# main.net
KiCad netlist of a schematic drawn in EAGLE
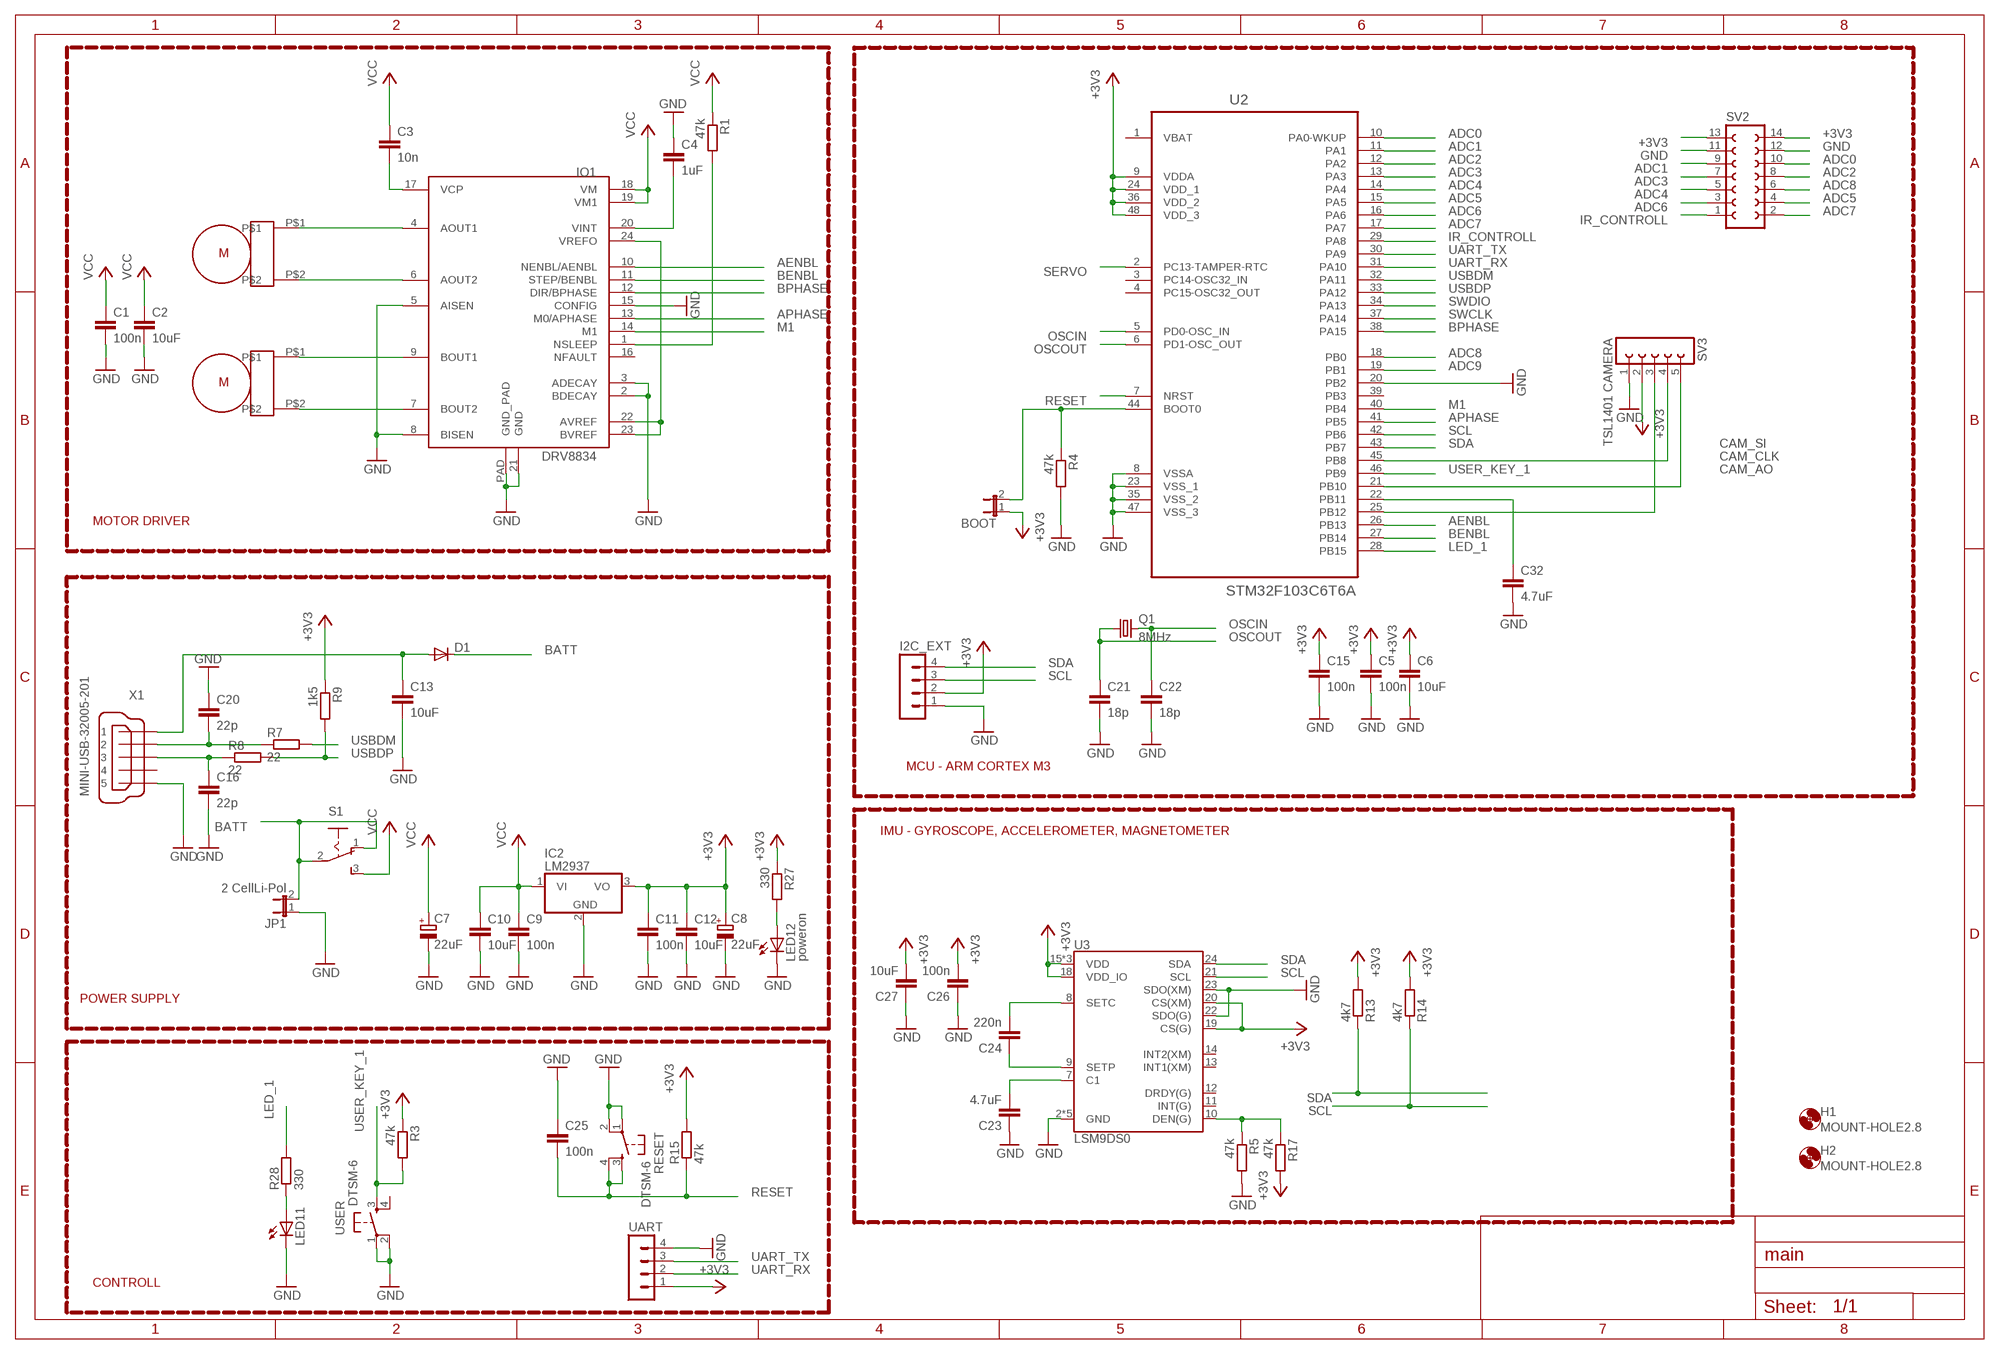
[diagram p0: schematic, sheet 1]

(export (version "E")
  (design (tool "Eeschema 10.0.6"))
  (components
    (comp (ref "BOOT")
      (value "JP1E")
      (footprint "eagle-import:JP1")
      (libsource (lib "eagle-import") (part "JP1E"))
    )
    (comp (ref "C1")
      (value "100n")
      (footprint "eagle-import:C1206")
      (libsource (lib "eagle-import") (part "C-EUC1206"))
    )
    (comp (ref "C2")
      (value "10uF")
      (footprint "eagle-import:C1206")
      (libsource (lib "eagle-import") (part "C-EUC1206"))
    )
    (comp (ref "C3")
      (value "10n")
      (footprint "eagle-import:C1206")
      (libsource (lib "eagle-import") (part "C-EUC1206"))
    )
    (comp (ref "C4")
      (value "1uF")
      (footprint "eagle-import:C1206")
      (libsource (lib "eagle-import") (part "C-EUC1206"))
    )
    (comp (ref "C5")
      (value "100n")
      (footprint "eagle-import:C0805")
      (libsource (lib "eagle-import") (part "C-EUC0805"))
    )
    (comp (ref "C6")
      (value "10uF")
      (footprint "eagle-import:C0805")
      (libsource (lib "eagle-import") (part "C-EUC0805"))
    )
    (comp (ref "C7")
      (value "22uF")
      (footprint "eagle-import:153CLV-0505")
      (libsource (lib "eagle-import") (part "CPOL-EU153CLV-0505"))
    )
    (comp (ref "C8")
      (value "22uF")
      (footprint "eagle-import:153CLV-0505")
      (libsource (lib "eagle-import") (part "CPOL-EU153CLV-0505"))
    )
    (comp (ref "C9")
      (value "100n")
      (footprint "eagle-import:C0805")
      (libsource (lib "eagle-import") (part "C-EUC0805"))
    )
    (comp (ref "C10")
      (value "10uF")
      (footprint "eagle-import:C0805")
      (libsource (lib "eagle-import") (part "C-EUC0805"))
    )
    (comp (ref "C11")
      (value "100n")
      (footprint "eagle-import:C0805")
      (libsource (lib "eagle-import") (part "C-EUC0805"))
    )
    (comp (ref "C12")
      (value "10uF")
      (footprint "eagle-import:C0805")
      (libsource (lib "eagle-import") (part "C-EUC0805"))
    )
    (comp (ref "C13")
      (value "10uF")
      (footprint "eagle-import:C0805")
      (libsource (lib "eagle-import") (part "C-EUC0805"))
    )
    (comp (ref "C15")
      (value "100n")
      (footprint "eagle-import:C0805")
      (libsource (lib "eagle-import") (part "C-EUC0805"))
    )
    (comp (ref "C16")
      (value "22p")
      (footprint "eagle-import:C0805")
      (libsource (lib "eagle-import") (part "C-EUC0805"))
    )
    (comp (ref "C20")
      (value "22p")
      (footprint "eagle-import:C0805")
      (libsource (lib "eagle-import") (part "C-EUC0805"))
    )
    (comp (ref "C21")
      (value "18p")
      (footprint "eagle-import:C0805")
      (libsource (lib "eagle-import") (part "C-EUC0805"))
    )
    (comp (ref "C22")
      (value "18p")
      (footprint "eagle-import:C0805")
      (libsource (lib "eagle-import") (part "C-EUC0805"))
    )
    (comp (ref "C23")
      (value "4.7uF")
      (footprint "eagle-import:C0805")
      (libsource (lib "eagle-import") (part "C-EUC0805"))
    )
    (comp (ref "C24")
      (value "220n")
      (footprint "eagle-import:C0805")
      (libsource (lib "eagle-import") (part "C-EUC0805"))
    )
    (comp (ref "C25")
      (value "100n")
      (footprint "eagle-import:C0805")
      (libsource (lib "eagle-import") (part "C-EUC0805"))
    )
    (comp (ref "C26")
      (value "100n")
      (footprint "eagle-import:C0805")
      (libsource (lib "eagle-import") (part "C-EUC0805"))
    )
    (comp (ref "C27")
      (value "10uF")
      (footprint "eagle-import:C0805")
      (libsource (lib "eagle-import") (part "C-EUC0805"))
    )
    (comp (ref "C32")
      (value "4.7uF")
      (footprint "eagle-import:C0805")
      (libsource (lib "eagle-import") (part "C-EUC0805"))
    )
    (comp (ref "D1")
      (value "DIODE-SMB")
      (footprint "eagle-import:SMB")
      (libsource (lib "eagle-import") (part "DIODE-SMB"))
    )
    (comp (ref "H1")
      (value "MOUNT-HOLE2.8")
      (footprint "eagle-import:2,8")
      (libsource (lib "eagle-import") (part "MOUNT-HOLE2.8"))
    )
    (comp (ref "H2")
      (value "MOUNT-HOLE2.8")
      (footprint "eagle-import:2,8")
      (libsource (lib "eagle-import") (part "MOUNT-HOLE2.8"))
    )
    (comp (ref "I2C_EXT")
      (value "MA04-1")
      (footprint "eagle-import:MA04-1")
      (libsource (lib "eagle-import") (part "MA04-1"))
    )
    (comp (ref "IC2")
      (value "LM2937")
      (footprint "eagle-import:TO263-3")
      (libsource (lib "eagle-import") (part "LM2937"))
    )
    (comp (ref "IO1")
      (value "DRV8834")
      (footprint "eagle-import:DRV8834_PCK")
      (libsource (lib "eagle-import") (part "DRV8834"))
    )
    (comp (ref "JP1")
      (value "2 CellLi-Pol")
      (footprint "eagle-import:JP1")
      (libsource (lib "eagle-import") (part "JP1E"))
    )
    (comp (ref "LED11")
      (value "LEDCHIPLED_1206")
      (footprint "eagle-import:CHIPLED_1206")
      (libsource (lib "eagle-import") (part "LEDCHIPLED_1206"))
    )
    (comp (ref "LED12")
      (value "poweron")
      (footprint "eagle-import:CHIPLED_1206")
      (libsource (lib "eagle-import") (part "LEDCHIPLED_1206"))
    )
    (comp (ref "Q1")
      (value "8MHz")
      (footprint "eagle-import:CTS406")
      (libsource (lib "eagle-import") (part "CRYSTALCTS406"))
    )
    (comp (ref "R1")
      (value "47k")
      (footprint "eagle-import:M1206")
      (libsource (lib "eagle-import") (part "R-EU_M1206"))
    )
    (comp (ref "R3")
      (value "47k")
      (footprint "eagle-import:M0805")
      (libsource (lib "eagle-import") (part "R-EU_M0805"))
    )
    (comp (ref "R4")
      (value "47k")
      (footprint "eagle-import:M0805")
      (libsource (lib "eagle-import") (part "R-EU_M0805"))
    )
    (comp (ref "R5")
      (value "47k")
      (footprint "eagle-import:M0805")
      (libsource (lib "eagle-import") (part "R-EU_M0805"))
    )
    (comp (ref "R7")
      (value "22")
      (footprint "eagle-import:M0805")
      (libsource (lib "eagle-import") (part "R-EU_M0805"))
    )
    (comp (ref "R8")
      (value "22")
      (footprint "eagle-import:M0805")
      (libsource (lib "eagle-import") (part "R-EU_M0805"))
    )
    (comp (ref "R9")
      (value "1k5")
      (footprint "eagle-import:M0805")
      (libsource (lib "eagle-import") (part "R-EU_M0805"))
    )
    (comp (ref "R13")
      (value "4k7")
      (footprint "eagle-import:M0805")
      (libsource (lib "eagle-import") (part "R-EU_M0805"))
    )
    (comp (ref "R14")
      (value "4k7")
      (footprint "eagle-import:M0805")
      (libsource (lib "eagle-import") (part "R-EU_M0805"))
    )
    (comp (ref "R15")
      (value "47k")
      (footprint "eagle-import:M0805")
      (libsource (lib "eagle-import") (part "R-EU_M0805"))
    )
    (comp (ref "R17")
      (value "47k")
      (footprint "eagle-import:M0805")
      (libsource (lib "eagle-import") (part "R-EU_M0805"))
    )
    (comp (ref "R27")
      (value "330")
      (footprint "eagle-import:M0805")
      (libsource (lib "eagle-import") (part "R-EU_M0805"))
    )
    (comp (ref "R28")
      (value "330")
      (footprint "eagle-import:M0805")
      (libsource (lib "eagle-import") (part "R-EU_M0805"))
    )
    (comp (ref "RESET")
      (value "DTSM-6")
      (footprint "eagle-import:DTSM-6")
      (libsource (lib "eagle-import") (part "DTSM-6"))
    )
    (comp (ref "S1")
      (value "255SB")
      (footprint "eagle-import:255SB")
      (libsource (lib "eagle-import") (part "255SB"))
    )
    (comp (ref "SV2")
      (value "FE07-2")
      (footprint "eagle-import:FE07-2")
      (libsource (lib "eagle-import") (part "FE07-2"))
    )
    (comp (ref "SV3")
      (value "TSL1401 CAMERA")
      (footprint "eagle-import:FE05-1")
      (libsource (lib "eagle-import") (part "FE05-1"))
    )
    (comp (ref "U$1")
      (value "MICRO_METAL_GEAR_MOTOR")
      (footprint "eagle-import:MICRO_METAL_GEAR_MOTOR")
      (libsource (lib "eagle-import") (part "MICRO_METAL_GEAR_MOTOR"))
    )
    (comp (ref "U$2")
      (value "MICRO_METAL_GEAR_MOTOR")
      (footprint "eagle-import:MICRO_METAL_GEAR_MOTOR")
      (libsource (lib "eagle-import") (part "MICRO_METAL_GEAR_MOTOR"))
    )
    (comp (ref "U2")
      (value "STM32F103C6T6A")
      (footprint "eagle-import:QFP50P900X900X160-48N")
      (libsource (lib "eagle-import") (part "STM32F103C6T6A"))
    )
    (comp (ref "U3")
      (value "LSM9DS0")
      (footprint "eagle-import:LGA-24")
      (libsource (lib "eagle-import") (part "LSM9DS0"))
    )
    (comp (ref "UART")
      (value "MA04-1")
      (footprint "eagle-import:MA04-1")
      (libsource (lib "eagle-import") (part "MA04-1"))
    )
    (comp (ref "USER")
      (value "DTSM-6")
      (footprint "eagle-import:DTSM-6")
      (libsource (lib "eagle-import") (part "DTSM-6"))
    )
    (comp (ref "X1")
      (value "MINI-USB-32005-201")
      (footprint "eagle-import:32005-201")
      (libsource (lib "eagle-import") (part "MINI-USB-32005-201"))
    )
  )
  (nets
    (net (code "1") (name "+3V3") (class "Default")
      (node (ref "BOOT") (pin "1") (pinfunction "1_1") (pintype "passive"))
      (node (ref "C11") (pin "1") (pinfunction "1_1") (pintype "passive"))
      (node (ref "C12") (pin "1") (pinfunction "1_1") (pintype "passive"))
      (node (ref "C15") (pin "1") (pinfunction "1_1") (pintype "passive"))
      (node (ref "C26") (pin "2") (pinfunction "2_2") (pintype "passive"))
      (node (ref "C27") (pin "2") (pinfunction "2_2") (pintype "passive"))
      (node (ref "C5") (pin "1") (pinfunction "1_1") (pintype "passive"))
      (node (ref "C6") (pin "1") (pinfunction "1_1") (pintype "passive"))
      (node (ref "C8") (pin "+") (pinfunction "+_+") (pintype "passive"))
      (node (ref "I2C_EXT") (pin "2") (pinfunction "2_2") (pintype "passive"))
      (node (ref "IC2") (pin "3") (pinfunction "VO_3") (pintype "passive"))
      (node (ref "R13") (pin "2") (pinfunction "2_2") (pintype "passive"))
      (node (ref "R14") (pin "2") (pinfunction "2_2") (pintype "passive"))
      (node (ref "R15") (pin "2") (pinfunction "2_2") (pintype "passive"))
      (node (ref "R17") (pin "2") (pinfunction "2_2") (pintype "passive"))
      (node (ref "R27") (pin "1") (pinfunction "1_1") (pintype "passive"))
      (node (ref "R3") (pin "1") (pinfunction "1_1") (pintype "passive"))
      (node (ref "R9") (pin "1") (pinfunction "1_1") (pintype "passive"))
      (node (ref "SV2") (pin "13") (pinfunction "13_13") (pintype "passive"))
      (node (ref "SV2") (pin "14") (pinfunction "14_14") (pintype "passive"))
      (node (ref "SV3") (pin "2") (pinfunction "2_2") (pintype "passive"))
      (node (ref "U2") (pin "24") (pinfunction "VDD_1_24") (pintype "power_in"))
      (node (ref "U2") (pin "36") (pinfunction "VDD_2_36") (pintype "power_in"))
      (node (ref "U2") (pin "48") (pinfunction "VDD_3_48") (pintype "power_in"))
      (node (ref "U2") (pin "9") (pinfunction "VDDA_9") (pintype "power_in"))
      (node (ref "U3") (pin "15") (pinfunction "VDD_15") (pintype "bidirectional"))
      (node (ref "U3") (pin "16") (pinfunction "VDD_16") (pintype "bidirectional"))
      (node (ref "U3") (pin "17") (pinfunction "VDD_17") (pintype "bidirectional"))
      (node (ref "U3") (pin "18") (pinfunction "VDD_IO_18") (pintype "bidirectional"))
      (node (ref "U3") (pin "19") (pinfunction "CS(G)_19") (pintype "bidirectional"))
      (node (ref "U3") (pin "20") (pinfunction "CS(XM)_20") (pintype "bidirectional"))
      (node (ref "UART") (pin "1") (pinfunction "1_1") (pintype "passive"))
    )
    (net (code "2") (name "/ADC0") (class "Default")
      (node (ref "SV2") (pin "10") (pinfunction "10_10") (pintype "passive"))
      (node (ref "U2") (pin "10") (pinfunction "PA0-WKUP_10") (pintype "bidirectional"))
    )
    (net (code "3") (name "/ADC1") (class "Default")
      (node (ref "SV2") (pin "9") (pinfunction "9_9") (pintype "passive"))
      (node (ref "U2") (pin "11") (pinfunction "PA1_11") (pintype "bidirectional"))
    )
    (net (code "4") (name "/ADC2") (class "Default")
      (node (ref "SV2") (pin "8") (pinfunction "8_8") (pintype "passive"))
      (node (ref "U2") (pin "12") (pinfunction "PA2_12") (pintype "bidirectional"))
    )
    (net (code "5") (name "/ADC3") (class "Default")
      (node (ref "SV2") (pin "7") (pinfunction "7_7") (pintype "passive"))
      (node (ref "U2") (pin "13") (pinfunction "PA3_13") (pintype "bidirectional"))
    )
    (net (code "6") (name "/ADC4") (class "Default")
      (node (ref "SV2") (pin "5") (pinfunction "5_5") (pintype "passive"))
      (node (ref "U2") (pin "14") (pinfunction "PA4_14") (pintype "bidirectional"))
    )
    (net (code "7") (name "/ADC5") (class "Default")
      (node (ref "SV2") (pin "4") (pinfunction "4_4") (pintype "passive"))
      (node (ref "U2") (pin "15") (pinfunction "PA5_15") (pintype "bidirectional"))
    )
    (net (code "8") (name "/ADC6") (class "Default")
      (node (ref "SV2") (pin "3") (pinfunction "3_3") (pintype "passive"))
      (node (ref "U2") (pin "16") (pinfunction "PA6_16") (pintype "bidirectional"))
    )
    (net (code "9") (name "/ADC7") (class "Default")
      (node (ref "SV2") (pin "2") (pinfunction "2_2") (pintype "passive"))
      (node (ref "U2") (pin "17") (pinfunction "PA7_17") (pintype "bidirectional"))
    )
    (net (code "10") (name "/ADC8") (class "Default")
      (node (ref "SV2") (pin "6") (pinfunction "6_6") (pintype "passive"))
      (node (ref "U2") (pin "18") (pinfunction "PB0_18") (pintype "bidirectional"))
    )
    (net (code "11") (name "/ADC9") (class "Default")
      (node (ref "U2") (pin "19") (pinfunction "PB1_19") (pintype "bidirectional"))
    )
    (net (code "12") (name "/AENBL") (class "Default")
      (node (ref "IO1") (pin "10") (pinfunction "NENBL/AENBL_10") (pintype "bidirectional"))
      (node (ref "U2") (pin "26") (pinfunction "PB13_26") (pintype "bidirectional"))
    )
    (net (code "13") (name "/APHASE") (class "Default")
      (node (ref "IO1") (pin "13") (pinfunction "M0/APHASE_13") (pintype "bidirectional"))
      (node (ref "U2") (pin "41") (pinfunction "PB5_41") (pintype "bidirectional"))
    )
    (net (code "14") (name "/BATT") (class "Default")
      (node (ref "D1") (pin "C") (pinfunction "C_C") (pintype "passive"))
      (node (ref "JP1") (pin "2") (pinfunction "2_2") (pintype "passive"))
      (node (ref "S1") (pin "1") (pinfunction "O_1") (pintype "passive"))
      (node (ref "S1") (pin "2") (pinfunction "P_2") (pintype "passive"))
    )
    (net (code "15") (name "/BENBL") (class "Default")
      (node (ref "IO1") (pin "11") (pinfunction "STEP/BENBL_11") (pintype "bidirectional"))
      (node (ref "U2") (pin "27") (pinfunction "PB14_27") (pintype "bidirectional"))
    )
    (net (code "16") (name "/BPHASE") (class "Default")
      (node (ref "IO1") (pin "12") (pinfunction "DIR/BPHASE_12") (pintype "bidirectional"))
      (node (ref "U2") (pin "38") (pinfunction "PA15_38") (pintype "bidirectional"))
    )
    (net (code "17") (name "/CAM_AO") (class "Default")
      (node (ref "SV3") (pin "3") (pinfunction "3_3") (pintype "passive"))
      (node (ref "U2") (pin "25") (pinfunction "PB12_25") (pintype "bidirectional"))
    )
    (net (code "18") (name "/CAM_CLK") (class "Default")
      (node (ref "SV3") (pin "4") (pinfunction "4_4") (pintype "passive"))
      (node (ref "U2") (pin "45") (pinfunction "PB8_45") (pintype "bidirectional"))
    )
    (net (code "19") (name "/CAM_SI") (class "Default")
      (node (ref "SV3") (pin "5") (pinfunction "5_5") (pintype "passive"))
      (node (ref "U2") (pin "21") (pinfunction "PB10_21") (pintype "bidirectional"))
    )
    (net (code "20") (name "/IR_CONTROLL") (class "Default")
      (node (ref "SV2") (pin "1") (pinfunction "1_1") (pintype "passive"))
      (node (ref "U2") (pin "29") (pinfunction "PA8_29") (pintype "bidirectional"))
    )
    (net (code "21") (name "/LED_1") (class "Default")
      (node (ref "R28") (pin "2") (pinfunction "2_2") (pintype "passive"))
      (node (ref "U2") (pin "28") (pinfunction "PB15_28") (pintype "bidirectional"))
    )
    (net (code "22") (name "/M1") (class "Default")
      (node (ref "IO1") (pin "14") (pinfunction "M1_14") (pintype "bidirectional"))
      (node (ref "U2") (pin "40") (pinfunction "PB4_40") (pintype "bidirectional"))
    )
    (net (code "23") (name "/OSCIN") (class "Default")
      (node (ref "C22") (pin "1") (pinfunction "1_1") (pintype "passive"))
      (node (ref "Q1") (pin "3") (pinfunction "2_3") (pintype "passive"))
      (node (ref "U2") (pin "5") (pinfunction "PD0-OSC_IN_5") (pintype "bidirectional"))
    )
    (net (code "24") (name "/OSCOUT") (class "Default")
      (node (ref "C21") (pin "1") (pinfunction "1_1") (pintype "passive"))
      (node (ref "Q1") (pin "1") (pinfunction "1_1") (pintype "passive"))
      (node (ref "U2") (pin "6") (pinfunction "PD1-OSC_OUT_6") (pintype "bidirectional"))
    )
    (net (code "25") (name "/RESET") (class "Default")
      (node (ref "C25") (pin "2") (pinfunction "2_2") (pintype "passive"))
      (node (ref "R15") (pin "1") (pinfunction "1_1") (pintype "passive"))
      (node (ref "RESET") (pin "3") (pinfunction "3_3") (pintype "passive"))
      (node (ref "RESET") (pin "4") (pinfunction "4_4") (pintype "passive"))
      (node (ref "U2") (pin "7") (pinfunction "NRST_7") (pintype "bidirectional"))
    )
    (net (code "26") (name "/SCL") (class "Default")
      (node (ref "I2C_EXT") (pin "3") (pinfunction "3_3") (pintype "passive"))
      (node (ref "R14") (pin "1") (pinfunction "1_1") (pintype "passive"))
      (node (ref "U2") (pin "42") (pinfunction "PB6_42") (pintype "bidirectional"))
      (node (ref "U3") (pin "21") (pinfunction "SCL_21") (pintype "bidirectional"))
    )
    (net (code "27") (name "/SDA") (class "Default")
      (node (ref "I2C_EXT") (pin "4") (pinfunction "4_4") (pintype "passive"))
      (node (ref "R13") (pin "1") (pinfunction "1_1") (pintype "passive"))
      (node (ref "U2") (pin "43") (pinfunction "PB7_43") (pintype "bidirectional"))
      (node (ref "U3") (pin "24") (pinfunction "SDA_24") (pintype "bidirectional"))
    )
    (net (code "28") (name "/SERVO") (class "Default")
      (node (ref "U2") (pin "2") (pinfunction "PC13-TAMPER-RTC_2") (pintype "bidirectional"))
    )
    (net (code "29") (name "/SWCLK") (class "Default")
      (node (ref "U2") (pin "37") (pinfunction "PA14_37") (pintype "bidirectional"))
    )
    (net (code "30") (name "/SWDIO") (class "Default")
      (node (ref "U2") (pin "34") (pinfunction "PA13_34") (pintype "bidirectional"))
    )
    (net (code "31") (name "/UART_RX") (class "Default")
      (node (ref "U2") (pin "31") (pinfunction "PA10_31") (pintype "bidirectional"))
      (node (ref "UART") (pin "2") (pinfunction "2_2") (pintype "passive"))
    )
    (net (code "32") (name "/UART_TX") (class "Default")
      (node (ref "U2") (pin "30") (pinfunction "PA9_30") (pintype "bidirectional"))
      (node (ref "UART") (pin "3") (pinfunction "3_3") (pintype "passive"))
    )
    (net (code "33") (name "/USBDM") (class "Default")
      (node (ref "R7") (pin "2") (pinfunction "2_2") (pintype "passive"))
      (node (ref "U2") (pin "32") (pinfunction "PA11_32") (pintype "bidirectional"))
    )
    (net (code "34") (name "/USBDP") (class "Default")
      (node (ref "R8") (pin "2") (pinfunction "2_2") (pintype "passive"))
      (node (ref "R9") (pin "2") (pinfunction "2_2") (pintype "passive"))
      (node (ref "U2") (pin "33") (pinfunction "PA12_33") (pintype "bidirectional"))
    )
    (net (code "35") (name "/USER_KEY_1") (class "Default")
      (node (ref "R3") (pin "2") (pinfunction "2_2") (pintype "passive"))
      (node (ref "U2") (pin "46") (pinfunction "PB9_46") (pintype "bidirectional"))
      (node (ref "USER") (pin "3") (pinfunction "3_3") (pintype "passive"))
    )
    (net (code "36") (name "/VBAT") (class "Default")
      (node (ref "U2") (pin "1") (pinfunction "VBAT_1") (pintype "power_in"))
    )
    (net (code "37") (name "GND") (class "Default")
      (node (ref "C1") (pin "2") (pinfunction "2_2") (pintype "passive"))
      (node (ref "C10") (pin "2") (pinfunction "2_2") (pintype "passive"))
      (node (ref "C11") (pin "2") (pinfunction "2_2") (pintype "passive"))
      (node (ref "C12") (pin "2") (pinfunction "2_2") (pintype "passive"))
      (node (ref "C13") (pin "2") (pinfunction "2_2") (pintype "passive"))
      (node (ref "C15") (pin "2") (pinfunction "2_2") (pintype "passive"))
      (node (ref "C16") (pin "2") (pinfunction "2_2") (pintype "passive"))
      (node (ref "C2") (pin "2") (pinfunction "2_2") (pintype "passive"))
      (node (ref "C20") (pin "1") (pinfunction "1_1") (pintype "passive"))
      (node (ref "C21") (pin "2") (pinfunction "2_2") (pintype "passive"))
      (node (ref "C22") (pin "2") (pinfunction "2_2") (pintype "passive"))
      (node (ref "C23") (pin "1") (pinfunction "1_1") (pintype "passive"))
      (node (ref "C25") (pin "1") (pinfunction "1_1") (pintype "passive"))
      (node (ref "C26") (pin "1") (pinfunction "1_1") (pintype "passive"))
      (node (ref "C27") (pin "1") (pinfunction "1_1") (pintype "passive"))
      (node (ref "C32") (pin "2") (pinfunction "2_2") (pintype "passive"))
      (node (ref "C4") (pin "1") (pinfunction "1_1") (pintype "passive"))
      (node (ref "C5") (pin "2") (pinfunction "2_2") (pintype "passive"))
      (node (ref "C6") (pin "2") (pinfunction "2_2") (pintype "passive"))
      (node (ref "C7") (pin "-") (pinfunction "-_-") (pintype "passive"))
      (node (ref "C8") (pin "-") (pinfunction "-_-") (pintype "passive"))
      (node (ref "C9") (pin "2") (pinfunction "2_2") (pintype "passive"))
      (node (ref "I2C_EXT") (pin "1") (pinfunction "1_1") (pintype "passive"))
      (node (ref "IC2") (pin "2") (pinfunction "GND_2") (pintype "passive"))
      (node (ref "IO1") (pin "15") (pinfunction "CONFIG_15") (pintype "bidirectional"))
      (node (ref "IO1") (pin "2") (pinfunction "BDECAY_2") (pintype "bidirectional"))
      (node (ref "IO1") (pin "21") (pinfunction "GND_21") (pintype "bidirectional"))
      (node (ref "IO1") (pin "3") (pinfunction "ADECAY_3") (pintype "bidirectional"))
      (node (ref "IO1") (pin "5") (pinfunction "AISEN_5") (pintype "bidirectional"))
      (node (ref "IO1") (pin "8") (pinfunction "BISEN_8") (pintype "bidirectional"))
      (node (ref "IO1") (pin "PAD") (pinfunction "GND_PAD_PAD") (pintype "bidirectional"))
      (node (ref "JP1") (pin "1") (pinfunction "1_1") (pintype "passive"))
      (node (ref "LED11") (pin "C") (pinfunction "C_C") (pintype "passive"))
      (node (ref "LED12") (pin "C") (pinfunction "C_C") (pintype "passive"))
      (node (ref "R4") (pin "2") (pinfunction "2_2") (pintype "passive"))
      (node (ref "R5") (pin "2") (pinfunction "2_2") (pintype "passive"))
      (node (ref "RESET") (pin "1") (pinfunction "1_1") (pintype "passive"))
      (node (ref "RESET") (pin "2") (pinfunction "2_2") (pintype "passive"))
      (node (ref "SV2") (pin "11") (pinfunction "11_11") (pintype "passive"))
      (node (ref "SV2") (pin "12") (pinfunction "12_12") (pintype "passive"))
      (node (ref "SV3") (pin "1") (pinfunction "1_1") (pintype "passive"))
      (node (ref "U2") (pin "20") (pinfunction "PB2_20") (pintype "bidirectional"))
      (node (ref "U2") (pin "23") (pinfunction "VSS_1_23") (pintype "passive"))
      (node (ref "U2") (pin "35") (pinfunction "VSS_2_35") (pintype "passive"))
      (node (ref "U2") (pin "47") (pinfunction "VSS_3_47") (pintype "passive"))
      (node (ref "U2") (pin "8") (pinfunction "VSSA_8") (pintype "passive"))
      (node (ref "U3") (pin "2") (pinfunction "GND_2") (pintype "bidirectional"))
      (node (ref "U3") (pin "22") (pinfunction "SDO(G)_22") (pintype "bidirectional"))
      (node (ref "U3") (pin "23") (pinfunction "SDO(XM)_23") (pintype "bidirectional"))
      (node (ref "U3") (pin "3") (pinfunction "GND_3") (pintype "bidirectional"))
      (node (ref "U3") (pin "4") (pinfunction "GND_4") (pintype "bidirectional"))
      (node (ref "U3") (pin "5") (pinfunction "GND_5") (pintype "bidirectional"))
      (node (ref "U3") (pin "6") (pinfunction "GND_6") (pintype "bidirectional"))
      (node (ref "UART") (pin "4") (pinfunction "4_4") (pintype "passive"))
      (node (ref "USER") (pin "1") (pinfunction "1_1") (pintype "passive"))
      (node (ref "USER") (pin "2") (pinfunction "2_2") (pintype "passive"))
      (node (ref "X1") (pin "5") (pinfunction "5_5") (pintype "passive"))
    )
    (net (code "38") (name "Net-(C13-Pad1)") (class "Default")
      (node (ref "C13") (pin "1") (pinfunction "1_1") (pintype "passive"))
      (node (ref "D1") (pin "A") (pinfunction "A_A") (pintype "passive"))
      (node (ref "X1") (pin "1") (pinfunction "1_1") (pintype "passive"))
    )
    (net (code "39") (name "Net-(C16-Pad1)") (class "Default")
      (node (ref "C16") (pin "1") (pinfunction "1_1") (pintype "passive"))
      (node (ref "R8") (pin "1") (pinfunction "1_1") (pintype "passive"))
      (node (ref "X1") (pin "3") (pinfunction "3_3") (pintype "passive"))
    )
    (net (code "40") (name "Net-(C20-Pad2)") (class "Default")
      (node (ref "C20") (pin "2") (pinfunction "2_2") (pintype "passive"))
      (node (ref "R7") (pin "1") (pinfunction "1_1") (pintype "passive"))
      (node (ref "X1") (pin "2") (pinfunction "2_2") (pintype "passive"))
    )
    (net (code "41") (name "Net-(IO1-AOUT1)") (class "Default")
      (node (ref "IO1") (pin "4") (pinfunction "AOUT1_4") (pintype "bidirectional"))
      (node (ref "U$1") (pin "P$1") (pinfunction "P$1_P$1") (pintype "bidirectional"))
    )
    (net (code "42") (name "Net-(IO1-AOUT2)") (class "Default")
      (node (ref "IO1") (pin "6") (pinfunction "AOUT2_6") (pintype "bidirectional"))
      (node (ref "U$1") (pin "P$2") (pinfunction "P$2_P$2") (pintype "bidirectional"))
    )
    (net (code "43") (name "Net-(IO1-AVREF)") (class "Default")
      (node (ref "IO1") (pin "22") (pinfunction "AVREF_22") (pintype "bidirectional"))
      (node (ref "IO1") (pin "23") (pinfunction "BVREF_23") (pintype "bidirectional"))
      (node (ref "IO1") (pin "24") (pinfunction "VREFO_24") (pintype "bidirectional"))
    )
    (net (code "44") (name "Net-(IO1-BOUT1)") (class "Default")
      (node (ref "IO1") (pin "9") (pinfunction "BOUT1_9") (pintype "bidirectional"))
      (node (ref "U$2") (pin "P$1") (pinfunction "P$1_P$1") (pintype "bidirectional"))
    )
    (net (code "45") (name "Net-(IO1-BOUT2)") (class "Default")
      (node (ref "IO1") (pin "7") (pinfunction "BOUT2_7") (pintype "bidirectional"))
      (node (ref "U$2") (pin "P$2") (pinfunction "P$2_P$2") (pintype "bidirectional"))
    )
    (net (code "46") (name "Net-(IO1-NSLEEP)") (class "Default")
      (node (ref "IO1") (pin "1") (pinfunction "NSLEEP_1") (pintype "bidirectional"))
      (node (ref "R1") (pin "2") (pinfunction "2_2") (pintype "passive"))
    )
    (net (code "47") (name "Net-(IO1-VCP)") (class "Default")
      (node (ref "C3") (pin "2") (pinfunction "2_2") (pintype "passive"))
      (node (ref "IO1") (pin "17") (pinfunction "VCP_17") (pintype "bidirectional"))
    )
    (net (code "48") (name "Net-(IO1-VINT)") (class "Default")
      (node (ref "C4") (pin "2") (pinfunction "2_2") (pintype "passive"))
      (node (ref "IO1") (pin "20") (pinfunction "VINT_20") (pintype "bidirectional"))
    )
    (net (code "49") (name "Net-(LED11-PadA)") (class "Default")
      (node (ref "LED11") (pin "A") (pinfunction "A_A") (pintype "passive"))
      (node (ref "R28") (pin "1") (pinfunction "1_1") (pintype "passive"))
    )
    (net (code "50") (name "Net-(LED12-PadA)") (class "Default")
      (node (ref "LED12") (pin "A") (pinfunction "A_A") (pintype "passive"))
      (node (ref "R27") (pin "2") (pinfunction "2_2") (pintype "passive"))
    )
    (net (code "51") (name "Net-(U2-BOOT0)") (class "Default")
      (node (ref "BOOT") (pin "2") (pinfunction "2_2") (pintype "passive"))
      (node (ref "R4") (pin "1") (pinfunction "1_1") (pintype "passive"))
      (node (ref "U2") (pin "44") (pinfunction "BOOT0_44") (pintype "input"))
    )
    (net (code "52") (name "Net-(U2-PB11)") (class "Default")
      (node (ref "C32") (pin "1") (pinfunction "1_1") (pintype "passive"))
      (node (ref "U2") (pin "22") (pinfunction "PB11_22") (pintype "bidirectional"))
    )
    (net (code "53") (name "Net-(U3-C1)") (class "Default")
      (node (ref "C23") (pin "2") (pinfunction "2_2") (pintype "passive"))
      (node (ref "U3") (pin "7") (pinfunction "C1_7") (pintype "bidirectional"))
    )
    (net (code "54") (name "Net-(U3-DEN(G))") (class "Default")
      (node (ref "R17") (pin "1") (pinfunction "1_1") (pintype "passive"))
      (node (ref "R5") (pin "1") (pinfunction "1_1") (pintype "passive"))
      (node (ref "U3") (pin "10") (pinfunction "DEN(G)_10") (pintype "bidirectional"))
    )
    (net (code "55") (name "Net-(U3-SETC)") (class "Default")
      (node (ref "C24") (pin "2") (pinfunction "2_2") (pintype "passive"))
      (node (ref "U3") (pin "8") (pinfunction "SETC_8") (pintype "bidirectional"))
    )
    (net (code "56") (name "Net-(U3-SETP)") (class "Default")
      (node (ref "C24") (pin "1") (pinfunction "1_1") (pintype "passive"))
      (node (ref "U3") (pin "9") (pinfunction "SETP_9") (pintype "bidirectional"))
    )
    (net (code "57") (name "VCC") (class "Default")
      (node (ref "C1") (pin "1") (pinfunction "1_1") (pintype "passive"))
      (node (ref "C10") (pin "1") (pinfunction "1_1") (pintype "passive"))
      (node (ref "C2") (pin "1") (pinfunction "1_1") (pintype "passive"))
      (node (ref "C3") (pin "1") (pinfunction "1_1") (pintype "passive"))
      (node (ref "C7") (pin "+") (pinfunction "+_+") (pintype "passive"))
      (node (ref "C9") (pin "1") (pinfunction "1_1") (pintype "passive"))
      (node (ref "IC2") (pin "1") (pinfunction "VI_1") (pintype "input"))
      (node (ref "IO1") (pin "18") (pinfunction "VM_18") (pintype "bidirectional"))
      (node (ref "IO1") (pin "19") (pinfunction "VM1_19") (pintype "bidirectional"))
      (node (ref "R1") (pin "1") (pinfunction "1_1") (pintype "passive"))
      (node (ref "S1") (pin "3") (pinfunction "S_3") (pintype "passive"))
    )
    (net (code "58") (name "unconnected-(IO1-NFAULT-Pad16)") (class "Default")
      (node (ref "IO1") (pin "16") (pinfunction "NFAULT_16") (pintype "bidirectional"))
    )
    (net (code "59") (name "unconnected-(U2-PB3-Pad39)") (class "Default")
      (node (ref "U2") (pin "39") (pinfunction "PB3_39") (pintype "bidirectional"))
    )
    (net (code "60") (name "unconnected-(U2-PC14-OSC32_IN-Pad3)") (class "Default")
      (node (ref "U2") (pin "3") (pinfunction "PC14-OSC32_IN_3") (pintype "bidirectional"))
    )
    (net (code "61") (name "unconnected-(U2-PC15-OSC32_OUT-Pad4)") (class "Default")
      (node (ref "U2") (pin "4") (pinfunction "PC15-OSC32_OUT_4") (pintype "bidirectional"))
    )
    (net (code "62") (name "unconnected-(U3-DRDY(G)-Pad12)") (class "Default")
      (node (ref "U3") (pin "12") (pinfunction "DRDY(G)_12") (pintype "bidirectional"))
    )
    (net (code "63") (name "unconnected-(U3-INT(G)-Pad11)") (class "Default")
      (node (ref "U3") (pin "11") (pinfunction "INT(G)_11") (pintype "bidirectional"))
    )
    (net (code "64") (name "unconnected-(U3-INT1(XM)-Pad13)") (class "Default")
      (node (ref "U3") (pin "13") (pinfunction "INT1(XM)_13") (pintype "bidirectional"))
    )
    (net (code "65") (name "unconnected-(U3-INT2(XM)-Pad14)") (class "Default")
      (node (ref "U3") (pin "14") (pinfunction "INT2(XM)_14") (pintype "bidirectional"))
    )
    (net (code "66") (name "unconnected-(USER-Pad4)") (class "Default")
      (node (ref "USER") (pin "4") (pinfunction "4_4") (pintype "passive"))
    )
    (net (code "67") (name "unconnected-(X1-Pad4)") (class "Default")
      (node (ref "X1") (pin "4") (pinfunction "4_4") (pintype "passive"))
    )
  )
)
